# Aixcel_Tiny_Recon_Board_Page2.net
KiCad netlist of a schematic drawn in Altium Designer
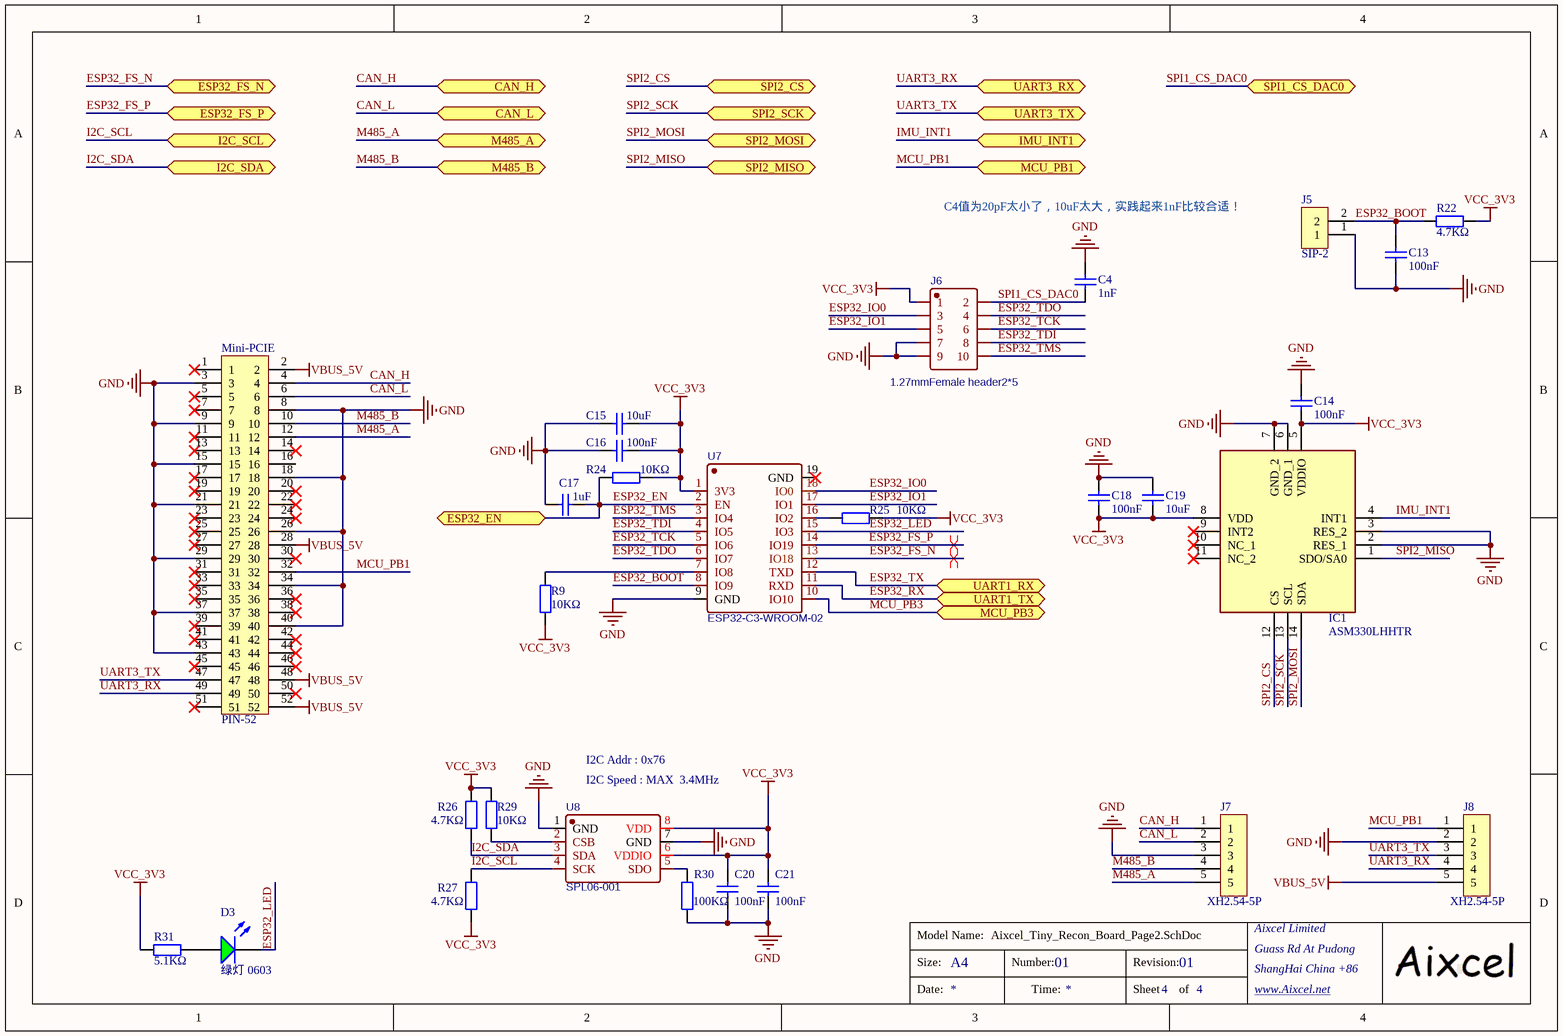
[diagram p0: Aixcel_Tiny_Recon_Board_Page2.SchDoc]

(export (version "E")
  (design (tool "Eeschema 10.0.6"))
  (components
    (comp (ref "C4")
      (value "1nF")
      (footprint "0603_C")
      (description "贴片电容")
      (libsource (lib "Miscellaneous Devices LC") (part "0603 1nF (102) 10% 50V"))
    )
    (comp (ref "C13")
      (value "100nF")
      (footprint "0603_C")
      (description "贴片电容")
      (libsource (lib "Miscellaneous Devices LC") (part "0603 100nF (104) 10% 50V"))
    )
    (comp (ref "C14")
      (value "100nF")
      (footprint "0603_C")
      (description "贴片电容")
      (libsource (lib "Miscellaneous Devices LC") (part "0603 100nF (104) 10% 50V"))
    )
    (comp (ref "C15")
      (value "10uF")
      (footprint "0603_C")
      (description "贴片电容")
      (libsource (lib "Miscellaneous Devices LC") (part "0603 10uF (106) 10% 10V"))
    )
    (comp (ref "C16")
      (value "100nF")
      (footprint "0603_C")
      (description "贴片电容")
      (libsource (lib "Miscellaneous Devices LC") (part "0603 100nF (104) 10% 50V"))
    )
    (comp (ref "C17")
      (value "1uF")
      (footprint "0603_C")
      (description "贴片电容")
      (libsource (lib "Miscellaneous Devices LC") (part "0603 1uF (105) 10% 50V"))
    )
    (comp (ref "C18")
      (value "100nF")
      (footprint "0603_C")
      (description "贴片电容")
      (libsource (lib "Miscellaneous Devices LC") (part "0603 100nF (104) 10% 50V"))
    )
    (comp (ref "C19")
      (value "10uF")
      (footprint "0603_C")
      (description "贴片电容")
      (libsource (lib "Miscellaneous Devices LC") (part "0603 10uF (106) 10% 10V"))
    )
    (comp (ref "C20")
      (value "100nF")
      (footprint "0603_C")
      (description "贴片电容")
      (libsource (lib "Miscellaneous Devices LC") (part "0603 100nF (104) 10% 50V"))
    )
    (comp (ref "C21")
      (value "100nF")
      (footprint "0603_C")
      (description "贴片电容")
      (libsource (lib "Miscellaneous Devices LC") (part "0603 100nF (104) 10% 50V"))
    )
    (comp (ref "D3")
      (value "绿灯 0603")
      (footprint "0603_LED_S1")
      (description "发光二极管")
      (libsource (lib "Miscellaneous Devices LC") (part "0603 绿灯"))
    )
    (comp (ref "IC1")
      (value "ASM330LHHTR")
      (footprint "SamacSys:LGA-14(2.5X3X0.86)")
      (description "Integrated Circuit")
      (fields (field (name "MOUSER2 PART NUMBER") "511-ASM330LHHTR"))
      (libsource (lib "*") (part "ASM330LHHTR"))
    )
    (comp (ref "J5") (value "SIP-2") (footprint "TSW SMD-3*6*2.5") (libsource (lib "接插件") (part "SIP-2")))
    (comp (ref "J6")
      (value "1.27mmFemale header2*5")
      (footprint "1.27mm_2_5排母")
      (fields (field (name "BOM_SUPPLIER PART") "C59983"))
      (libsource (lib "其他") (part "1.27mmFemale header2*5"))
    )
    (comp (ref "J7") (value "XH2.54-5P") (footprint "2.54XH接插件5P") (libsource (lib "接插件") (part "SIP-5")))
    (comp (ref "J8") (value "XH2.54-5P") (footprint "2.54XH接插件5P") (libsource (lib "接插件") (part "SIP-5")))
    (comp (ref "Mini-PCIE")
      (value "PIN-52")
      (footprint "PCBComponent_1")
      (libsource (lib "接插件") (part "PIN-52"))
    )
    (comp (ref "R9")
      (value "10KΩ")
      (footprint "0603_R")
      (description "贴片电阻")
      (libsource (lib "") (part "0603 10KΩ (1002) 1%_1"))
    )
    (comp (ref "R22")
      (value "4.7KΩ")
      (footprint "0603_R")
      (description "贴片电阻")
      (libsource (lib "") (part "0603 4.7KΩ (4701) 1%_1"))
    )
    (comp (ref "R24")
      (value "10KΩ")
      (footprint "0603_R")
      (description "贴片电阻")
      (libsource (lib "Miscellaneous Devices LC") (part "0603 10KΩ (1002) 1%"))
    )
    (comp (ref "R25")
      (value "10KΩ")
      (footprint "0603_R")
      (description "贴片电阻")
      (libsource (lib "Miscellaneous Devices LC") (part "0603 10KΩ (1002) 1%"))
    )
    (comp (ref "R26")
      (value "4.7KΩ")
      (footprint "0603_R")
      (description "贴片电阻")
      (libsource (lib "Miscellaneous Devices LC") (part "0603 4.7KΩ (4701) 1%"))
    )
    (comp (ref "R27")
      (value "4.7KΩ")
      (footprint "0603_R")
      (description "贴片电阻")
      (libsource (lib "Miscellaneous Devices LC") (part "0603 4.7KΩ (4701) 1%"))
    )
    (comp (ref "R29")
      (value "10KΩ")
      (footprint "0603_R")
      (description "贴片电阻")
      (libsource (lib "") (part "0603 10KΩ (1002) 1%_1"))
    )
    (comp (ref "R30")
      (value "100KΩ")
      (footprint "0603_R")
      (description "贴片电阻")
      (libsource (lib "Miscellaneous Devices LC") (part "0603 100KΩ (1003) 1%"))
    )
    (comp (ref "R31")
      (value "5.1KΩ")
      (footprint "0603_R")
      (description "贴片电阻")
      (libsource (lib "Miscellaneous Devices LC") (part "0603 5.1KΩ (5101) 1%"))
    )
    (comp (ref "U7")
      (value "ESP32-C3-WROOM-02")
      (footprint "WIFIM-SMD_19P-L18.0-W20.0-P1.50")
      (fields
        (field (name "BOM_SUPPLIER PART") "C529584")
        (field (name "BOM_MANUFACTURER PART") "ESP-WROOM-02D(4MB)")
        (field (name "CONTRIBUTOR") "LCSC")
      )
      (libsource (lib "其他") (part "ESP-C3-WROOM-02"))
    )
    (comp (ref "U8")
      (value "SPL06-001")
      (footprint "SPL06-001")
      (fields (field (name "BOM_SUPPLIER PART") "C2684428") (field (name "CONTRIBUTOR") "LCSC"))
      (libsource (lib "其他") (part "SPL06-001"))
    )
  )
  (nets
    (net (code "1") (name "/CAN_H") (class "Default")
      (node (ref "J7") (pin "1") (pinfunction "1_1") (pintype "passive"))
      (node (ref "Mini-PCIE") (pin "4") (pinfunction "4_4") (pintype "passive"))
    )
    (net (code "2") (name "/CAN_L") (class "Default")
      (node (ref "J7") (pin "2") (pinfunction "2_2") (pintype "passive"))
      (node (ref "Mini-PCIE") (pin "6") (pinfunction "6_6") (pintype "passive"))
    )
    (net (code "3") (name "/ESP32_BOOT") (class "Default")
      (node (ref "C13") (pin "2") (pinfunction "2_2") (pintype "passive"))
      (node (ref "J5") (pin "2") (pinfunction "2_2") (pintype "passive"))
      (node (ref "R22") (pin "1") (pinfunction "1_1") (pintype "passive"))
      (node (ref "U7") (pin "8") (pinfunction "IO9_8") (pintype "passive"))
    )
    (net (code "4") (name "/ESP32_EN") (class "Default")
      (node (ref "C17") (pin "1") (pinfunction "1_1") (pintype "passive"))
      (node (ref "R24") (pin "1") (pinfunction "1_1") (pintype "passive"))
      (node (ref "U7") (pin "2") (pinfunction "EN_2") (pintype "passive"))
    )
    (net (code "5") (name "/ESP32_FS_N") (class "Default")
      (node (ref "U7") (pin "13") (pinfunction "IO18_13") (pintype "passive"))
    )
    (net (code "6") (name "/ESP32_FS_P") (class "Default")
      (node (ref "U7") (pin "14") (pinfunction "IO19_14") (pintype "passive"))
    )
    (net (code "7") (name "/ESP32_IO0") (class "Default")
      (node (ref "J6") (pin "3") (pinfunction "3_3") (pintype "passive"))
      (node (ref "U7") (pin "18") (pinfunction "IO0_18") (pintype "passive"))
    )
    (net (code "8") (name "/ESP32_IO1") (class "Default")
      (node (ref "J6") (pin "5") (pinfunction "5_5") (pintype "passive"))
      (node (ref "U7") (pin "17") (pinfunction "IO1_17") (pintype "passive"))
    )
    (net (code "9") (name "/ESP32_LED") (class "Default")
      (node (ref "D3") (pin "K") (pinfunction "K_K") (pintype "passive"))
      (node (ref "U7") (pin "15") (pinfunction "IO3_15") (pintype "passive"))
    )
    (net (code "10") (name "/ESP32_RX") (class "Default")
      (node (ref "U7") (pin "11") (pinfunction "RXD_11") (pintype "passive"))
    )
    (net (code "11") (name "/ESP32_TCK") (class "Default")
      (node (ref "J6") (pin "6") (pinfunction "6_6") (pintype "passive"))
      (node (ref "U7") (pin "5") (pinfunction "IO6_5") (pintype "passive"))
    )
    (net (code "12") (name "/ESP32_TDI") (class "Default")
      (node (ref "J6") (pin "8") (pinfunction "8_8") (pintype "passive"))
      (node (ref "U7") (pin "4") (pinfunction "IO5_4") (pintype "passive"))
    )
    (net (code "13") (name "/ESP32_TDO") (class "Default")
      (node (ref "J6") (pin "4") (pinfunction "4_4") (pintype "passive"))
      (node (ref "U7") (pin "6") (pinfunction "IO7_6") (pintype "passive"))
    )
    (net (code "14") (name "/ESP32_TMS") (class "Default")
      (node (ref "J6") (pin "10") (pinfunction "10_10") (pintype "passive"))
      (node (ref "U7") (pin "3") (pinfunction "IO4_3") (pintype "passive"))
    )
    (net (code "15") (name "/ESP32_TX") (class "Default")
      (node (ref "U7") (pin "12") (pinfunction "TXD_12") (pintype "passive"))
    )
    (net (code "16") (name "/I2C_SCL") (class "Default")
      (node (ref "R27") (pin "2") (pinfunction "2_2") (pintype "passive"))
      (node (ref "U8") (pin "4") (pinfunction "SCK_4") (pintype "passive"))
    )
    (net (code "17") (name "/I2C_SDA") (class "Default")
      (node (ref "R26") (pin "1") (pinfunction "1_1") (pintype "passive"))
      (node (ref "U8") (pin "3") (pinfunction "SDA_3") (pintype "passive"))
    )
    (net (code "18") (name "/IMU_INT1") (class "Default")
      (node (ref "IC1") (pin "4") (pinfunction "INT1_4") (pintype "passive"))
    )
    (net (code "19") (name "/M485_A") (class "Default")
      (node (ref "J7") (pin "5") (pinfunction "5_5") (pintype "passive"))
      (node (ref "Mini-PCIE") (pin "12") (pinfunction "12_12") (pintype "passive"))
    )
    (net (code "20") (name "/M485_B") (class "Default")
      (node (ref "J7") (pin "4") (pinfunction "4_4") (pintype "passive"))
      (node (ref "Mini-PCIE") (pin "10") (pinfunction "10_10") (pintype "passive"))
    )
    (net (code "21") (name "/MCU_PB1") (class "Default")
      (node (ref "J8") (pin "1") (pinfunction "1_1") (pintype "passive"))
      (node (ref "Mini-PCIE") (pin "32") (pinfunction "32_32") (pintype "passive"))
    )
    (net (code "22") (name "/MCU_PB3") (class "Default")
      (node (ref "U7") (pin "10") (pinfunction "IO10_10") (pintype "passive"))
    )
    (net (code "23") (name "/SPI1_CS_DAC0") (class "Default")
      (node (ref "C4") (pin "1") (pinfunction "1_1") (pintype "passive"))
      (node (ref "J6") (pin "2") (pinfunction "2_2") (pintype "passive"))
    )
    (net (code "24") (name "/SPI2_CS") (class "Default")
      (node (ref "IC1") (pin "12") (pinfunction "CS_12") (pintype "passive"))
    )
    (net (code "25") (name "/SPI2_MISO") (class "Default")
      (node (ref "IC1") (pin "1") (pinfunction "SDO/SA0_1") (pintype "passive"))
    )
    (net (code "26") (name "/SPI2_MOSI") (class "Default")
      (node (ref "IC1") (pin "14") (pinfunction "SDA_14") (pintype "passive"))
    )
    (net (code "27") (name "/SPI2_SCK") (class "Default")
      (node (ref "IC1") (pin "13") (pinfunction "SCL_13") (pintype "passive"))
    )
    (net (code "28") (name "/UART3_RX") (class "Default")
      (node (ref "J8") (pin "4") (pinfunction "4_4") (pintype "passive"))
      (node (ref "Mini-PCIE") (pin "49") (pinfunction "49_49") (pintype "passive"))
    )
    (net (code "29") (name "/UART3_TX") (class "Default")
      (node (ref "J8") (pin "3") (pinfunction "3_3") (pintype "passive"))
      (node (ref "Mini-PCIE") (pin "47") (pinfunction "47_47") (pintype "passive"))
    )
    (net (code "30") (name "GND") (class "Default")
      (node (ref "C13") (pin "1") (pinfunction "1_1") (pintype "passive"))
      (node (ref "C14") (pin "2") (pinfunction "2_2") (pintype "passive"))
      (node (ref "C15") (pin "2") (pinfunction "2_2") (pintype "passive"))
      (node (ref "C16") (pin "2") (pinfunction "2_2") (pintype "passive"))
      (node (ref "C17") (pin "2") (pinfunction "2_2") (pintype "passive"))
      (node (ref "C18") (pin "2") (pinfunction "2_2") (pintype "passive"))
      (node (ref "C19") (pin "2") (pinfunction "2_2") (pintype "passive"))
      (node (ref "C20") (pin "1") (pinfunction "1_1") (pintype "passive"))
      (node (ref "C21") (pin "1") (pinfunction "1_1") (pintype "passive"))
      (node (ref "C4") (pin "2") (pinfunction "2_2") (pintype "passive"))
      (node (ref "IC1") (pin "2") (pinfunction "RES_1_2") (pintype "passive"))
      (node (ref "IC1") (pin "3") (pinfunction "RES_2_3") (pintype "passive"))
      (node (ref "IC1") (pin "6") (pinfunction "GND_1_6") (pintype "passive"))
      (node (ref "IC1") (pin "7") (pinfunction "GND_2_7") (pintype "passive"))
      (node (ref "J5") (pin "1") (pinfunction "1_1") (pintype "passive"))
      (node (ref "J6") (pin "7") (pinfunction "7_7") (pintype "passive"))
      (node (ref "J6") (pin "9") (pinfunction "9_9") (pintype "passive"))
      (node (ref "J7") (pin "3") (pinfunction "3_3") (pintype "passive"))
      (node (ref "J8") (pin "2") (pinfunction "2_2") (pintype "passive"))
      (node (ref "Mini-PCIE") (pin "15") (pinfunction "15_15") (pintype "passive"))
      (node (ref "Mini-PCIE") (pin "18") (pinfunction "18_18") (pintype "passive"))
      (node (ref "Mini-PCIE") (pin "21") (pinfunction "21_21") (pintype "passive"))
      (node (ref "Mini-PCIE") (pin "26") (pinfunction "26_26") (pintype "passive"))
      (node (ref "Mini-PCIE") (pin "29") (pinfunction "29_29") (pintype "passive"))
      (node (ref "Mini-PCIE") (pin "3") (pinfunction "3_3") (pintype "passive"))
      (node (ref "Mini-PCIE") (pin "34") (pinfunction "34_34") (pintype "passive"))
      (node (ref "Mini-PCIE") (pin "37") (pinfunction "37_37") (pintype "passive"))
      (node (ref "Mini-PCIE") (pin "40") (pinfunction "40_40") (pintype "passive"))
      (node (ref "Mini-PCIE") (pin "43") (pinfunction "43_43") (pintype "passive"))
      (node (ref "Mini-PCIE") (pin "8") (pinfunction "8_8") (pintype "passive"))
      (node (ref "Mini-PCIE") (pin "9") (pinfunction "9_9") (pintype "passive"))
      (node (ref "R30") (pin "1") (pinfunction "1_1") (pintype "passive"))
      (node (ref "U7") (pin "9") (pinfunction "GND_9") (pintype "passive"))
      (node (ref "U8") (pin "1") (pinfunction "GND_1") (pintype "passive"))
      (node (ref "U8") (pin "7") (pinfunction "GND_7") (pintype "passive"))
    )
    (net (code "31") (name "Net-(D3-PadA)") (class "Default")
      (node (ref "D3") (pin "A") (pinfunction "A_A") (pintype "passive"))
      (node (ref "R31") (pin "2") (pinfunction "2_2") (pintype "passive"))
    )
    (net (code "32") (name "Net-(U7-IO2)") (class "Default")
      (node (ref "R25") (pin "1") (pinfunction "1_1") (pintype "passive"))
      (node (ref "U7") (pin "16") (pinfunction "IO2_16") (pintype "passive"))
    )
    (net (code "33") (name "Net-(U7-IO8)") (class "Default")
      (node (ref "R9") (pin "2") (pinfunction "2_2") (pintype "passive"))
      (node (ref "U7") (pin "7") (pinfunction "IO8_7") (pintype "passive"))
    )
    (net (code "34") (name "Net-(U8-CSB)") (class "Default")
      (node (ref "R29") (pin "1") (pinfunction "1_1") (pintype "passive"))
      (node (ref "U8") (pin "2") (pinfunction "CSB_2") (pintype "passive"))
    )
    (net (code "35") (name "Net-(U8-SDO)") (class "Default")
      (node (ref "R30") (pin "2") (pinfunction "2_2") (pintype "passive"))
      (node (ref "U8") (pin "5") (pinfunction "SDO_5") (pintype "passive"))
    )
    (net (code "36") (name "VBUS_5V") (class "Default")
      (node (ref "J8") (pin "5") (pinfunction "5_5") (pintype "passive"))
      (node (ref "Mini-PCIE") (pin "2") (pinfunction "2_2") (pintype "passive"))
      (node (ref "Mini-PCIE") (pin "28") (pinfunction "28_28") (pintype "passive"))
      (node (ref "Mini-PCIE") (pin "48") (pinfunction "48_48") (pintype "passive"))
      (node (ref "Mini-PCIE") (pin "52") (pinfunction "52_52") (pintype "passive"))
    )
    (net (code "37") (name "VCC_3V3") (class "Default")
      (node (ref "C14") (pin "1") (pinfunction "1_1") (pintype "passive"))
      (node (ref "C15") (pin "1") (pinfunction "1_1") (pintype "passive"))
      (node (ref "C16") (pin "1") (pinfunction "1_1") (pintype "passive"))
      (node (ref "C18") (pin "1") (pinfunction "1_1") (pintype "passive"))
      (node (ref "C19") (pin "1") (pinfunction "1_1") (pintype "passive"))
      (node (ref "C20") (pin "2") (pinfunction "2_2") (pintype "passive"))
      (node (ref "C21") (pin "2") (pinfunction "2_2") (pintype "passive"))
      (node (ref "IC1") (pin "5") (pinfunction "VDDIO_5") (pintype "passive"))
      (node (ref "IC1") (pin "8") (pinfunction "VDD_8") (pintype "passive"))
      (node (ref "J6") (pin "1") (pinfunction "1_1") (pintype "passive"))
      (node (ref "R22") (pin "2") (pinfunction "2_2") (pintype "passive"))
      (node (ref "R24") (pin "2") (pinfunction "2_2") (pintype "passive"))
      (node (ref "R25") (pin "2") (pinfunction "2_2") (pintype "passive"))
      (node (ref "R26") (pin "2") (pinfunction "2_2") (pintype "passive"))
      (node (ref "R27") (pin "1") (pinfunction "1_1") (pintype "passive"))
      (node (ref "R29") (pin "2") (pinfunction "2_2") (pintype "passive"))
      (node (ref "R31") (pin "1") (pinfunction "1_1") (pintype "passive"))
      (node (ref "R9") (pin "1") (pinfunction "1_1") (pintype "passive"))
      (node (ref "U7") (pin "1") (pinfunction "3V3_1") (pintype "passive"))
      (node (ref "U8") (pin "6") (pinfunction "VDDIO_6") (pintype "passive"))
      (node (ref "U8") (pin "8") (pinfunction "VDD_8") (pintype "passive"))
    )
    (net (code "38") (name "unconnected-(IC1-INT2-Pad9)") (class "Default")
      (node (ref "IC1") (pin "9") (pinfunction "INT2_9") (pintype "passive+no_connect"))
    )
    (net (code "39") (name "unconnected-(IC1-NC_1-Pad10)") (class "Default")
      (node (ref "IC1") (pin "10") (pinfunction "NC_1_10") (pintype "passive+no_connect"))
    )
    (net (code "40") (name "unconnected-(IC1-NC_2-Pad11)") (class "Default")
      (node (ref "IC1") (pin "11") (pinfunction "NC_2_11") (pintype "passive+no_connect"))
    )
    (net (code "41") (name "unconnected-(Mini-PCIE-Pad1)") (class "Default")
      (node (ref "Mini-PCIE") (pin "1") (pinfunction "1_1") (pintype "passive+no_connect"))
    )
    (net (code "42") (name "unconnected-(Mini-PCIE-Pad5)") (class "Default")
      (node (ref "Mini-PCIE") (pin "5") (pinfunction "5_5") (pintype "passive+no_connect"))
    )
    (net (code "43") (name "unconnected-(Mini-PCIE-Pad7)") (class "Default")
      (node (ref "Mini-PCIE") (pin "7") (pinfunction "7_7") (pintype "passive+no_connect"))
    )
    (net (code "44") (name "unconnected-(Mini-PCIE-Pad11)") (class "Default")
      (node (ref "Mini-PCIE") (pin "11") (pinfunction "11_11") (pintype "passive+no_connect"))
    )
    (net (code "45") (name "unconnected-(Mini-PCIE-Pad13)") (class "Default")
      (node (ref "Mini-PCIE") (pin "13") (pinfunction "13_13") (pintype "passive+no_connect"))
    )
    (net (code "46") (name "unconnected-(Mini-PCIE-Pad14)") (class "Default")
      (node (ref "Mini-PCIE") (pin "14") (pinfunction "14_14") (pintype "passive+no_connect"))
    )
    (net (code "47") (name "unconnected-(Mini-PCIE-Pad16)") (class "Default")
      (node (ref "Mini-PCIE") (pin "16") (pinfunction "16_16") (pintype "passive"))
    )
    (net (code "48") (name "unconnected-(Mini-PCIE-Pad17)") (class "Default")
      (node (ref "Mini-PCIE") (pin "17") (pinfunction "17_17") (pintype "passive+no_connect"))
    )
    (net (code "49") (name "unconnected-(Mini-PCIE-Pad19)") (class "Default")
      (node (ref "Mini-PCIE") (pin "19") (pinfunction "19_19") (pintype "passive+no_connect"))
    )
    (net (code "50") (name "unconnected-(Mini-PCIE-Pad20)") (class "Default")
      (node (ref "Mini-PCIE") (pin "20") (pinfunction "20_20") (pintype "passive+no_connect"))
    )
    (net (code "51") (name "unconnected-(Mini-PCIE-Pad22)") (class "Default")
      (node (ref "Mini-PCIE") (pin "22") (pinfunction "22_22") (pintype "passive+no_connect"))
    )
    (net (code "52") (name "unconnected-(Mini-PCIE-Pad23)") (class "Default")
      (node (ref "Mini-PCIE") (pin "23") (pinfunction "23_23") (pintype "passive+no_connect"))
    )
    (net (code "53") (name "unconnected-(Mini-PCIE-Pad24)") (class "Default")
      (node (ref "Mini-PCIE") (pin "24") (pinfunction "24_24") (pintype "passive+no_connect"))
    )
    (net (code "54") (name "unconnected-(Mini-PCIE-Pad25)") (class "Default")
      (node (ref "Mini-PCIE") (pin "25") (pinfunction "25_25") (pintype "passive+no_connect"))
    )
    (net (code "55") (name "unconnected-(Mini-PCIE-Pad27)") (class "Default")
      (node (ref "Mini-PCIE") (pin "27") (pinfunction "27_27") (pintype "passive+no_connect"))
    )
    (net (code "56") (name "unconnected-(Mini-PCIE-Pad30)") (class "Default")
      (node (ref "Mini-PCIE") (pin "30") (pinfunction "30_30") (pintype "passive+no_connect"))
    )
    (net (code "57") (name "unconnected-(Mini-PCIE-Pad31)") (class "Default")
      (node (ref "Mini-PCIE") (pin "31") (pinfunction "31_31") (pintype "passive+no_connect"))
    )
    (net (code "58") (name "unconnected-(Mini-PCIE-Pad33)") (class "Default")
      (node (ref "Mini-PCIE") (pin "33") (pinfunction "33_33") (pintype "passive+no_connect"))
    )
    (net (code "59") (name "unconnected-(Mini-PCIE-Pad35)") (class "Default")
      (node (ref "Mini-PCIE") (pin "35") (pinfunction "35_35") (pintype "passive+no_connect"))
    )
    (net (code "60") (name "unconnected-(Mini-PCIE-Pad36)") (class "Default")
      (node (ref "Mini-PCIE") (pin "36") (pinfunction "36_36") (pintype "passive+no_connect"))
    )
    (net (code "61") (name "unconnected-(Mini-PCIE-Pad38)") (class "Default")
      (node (ref "Mini-PCIE") (pin "38") (pinfunction "38_38") (pintype "passive+no_connect"))
    )
    (net (code "62") (name "unconnected-(Mini-PCIE-Pad39)") (class "Default")
      (node (ref "Mini-PCIE") (pin "39") (pinfunction "39_39") (pintype "passive+no_connect"))
    )
    (net (code "63") (name "unconnected-(Mini-PCIE-Pad41)") (class "Default")
      (node (ref "Mini-PCIE") (pin "41") (pinfunction "41_41") (pintype "passive+no_connect"))
    )
    (net (code "64") (name "unconnected-(Mini-PCIE-Pad42)") (class "Default")
      (node (ref "Mini-PCIE") (pin "42") (pinfunction "42_42") (pintype "passive+no_connect"))
    )
    (net (code "65") (name "unconnected-(Mini-PCIE-Pad44)") (class "Default")
      (node (ref "Mini-PCIE") (pin "44") (pinfunction "44_44") (pintype "passive+no_connect"))
    )
    (net (code "66") (name "unconnected-(Mini-PCIE-Pad45)") (class "Default")
      (node (ref "Mini-PCIE") (pin "45") (pinfunction "45_45") (pintype "passive+no_connect"))
    )
    (net (code "67") (name "unconnected-(Mini-PCIE-Pad46)") (class "Default")
      (node (ref "Mini-PCIE") (pin "46") (pinfunction "46_46") (pintype "passive+no_connect"))
    )
    (net (code "68") (name "unconnected-(Mini-PCIE-Pad50)") (class "Default")
      (node (ref "Mini-PCIE") (pin "50") (pinfunction "50_50") (pintype "passive+no_connect"))
    )
    (net (code "69") (name "unconnected-(Mini-PCIE-Pad51)") (class "Default")
      (node (ref "Mini-PCIE") (pin "51") (pinfunction "51_51") (pintype "passive+no_connect"))
    )
    (net (code "70") (name "unconnected-(U7-GND-Pad19)") (class "Default")
      (node (ref "U7") (pin "19") (pinfunction "GND_19") (pintype "passive+no_connect"))
    )
  )
)
